# usb_shield.net
KiCad netlist of a schematic drawn in EAGLE
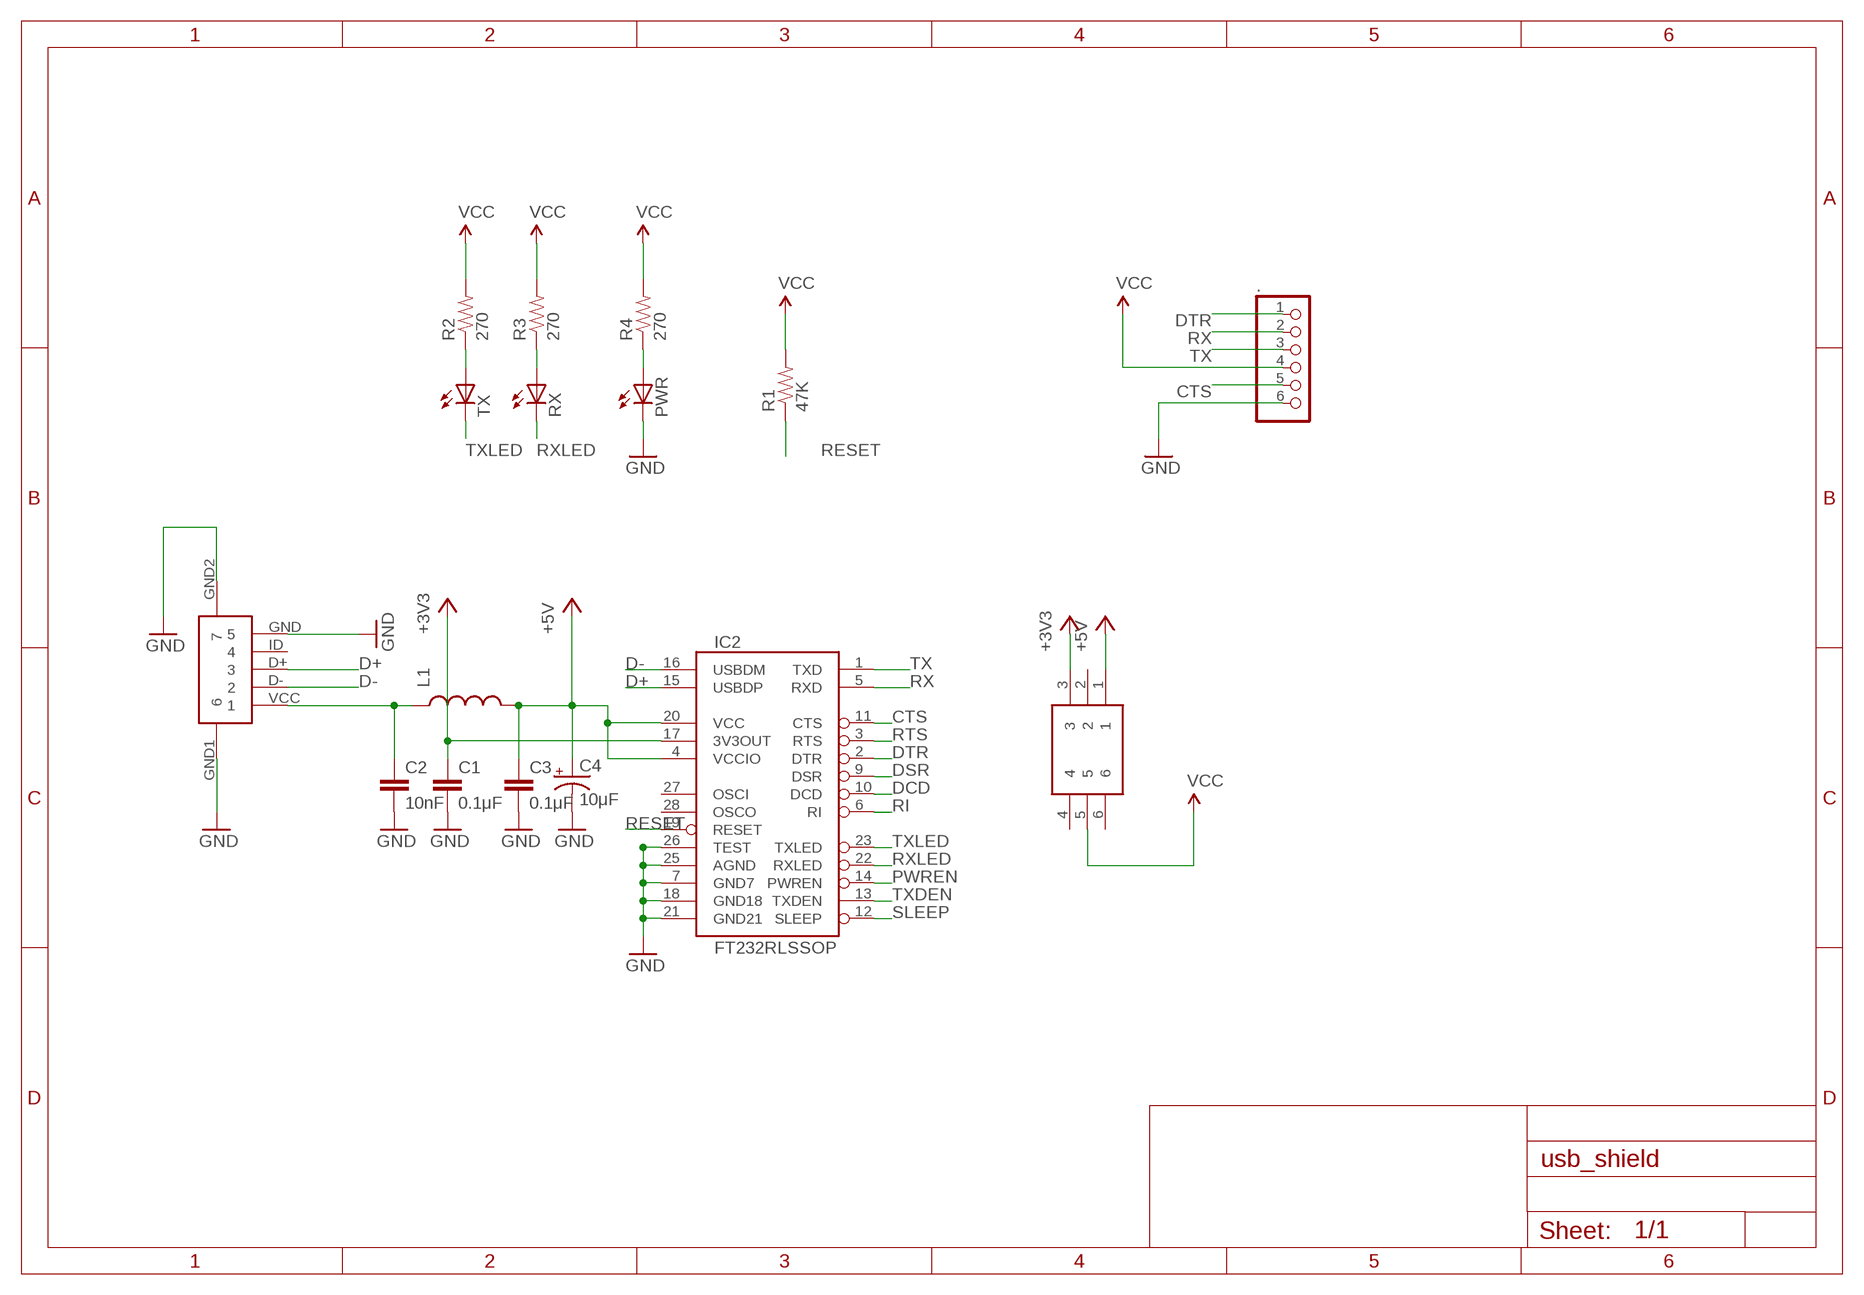
[diagram p0: schematic, sheet 1]

(export (version "E")
  (design (tool "Eeschema 10.0.6"))
  (components
    (comp (ref ".")
      (value "PINHD-1X6")
      (footprint "eagle-import:1X06")
      (libsource (lib "eagle-import") (part "PINHD-1X6"))
    )
    (comp (ref "C1")
      (value "0.1μF")
      (footprint "eagle-import:0603-CAP")
      (libsource (lib "eagle-import") (part "CAP0603-CAP"))
    )
    (comp (ref "C2")
      (value "10nF")
      (footprint "eagle-import:0603-CAP")
      (libsource (lib "eagle-import") (part "CAP0603-CAP"))
    )
    (comp (ref "C3")
      (value "0.1μF")
      (footprint "eagle-import:0603-CAP")
      (libsource (lib "eagle-import") (part "CAP0603-CAP"))
    )
    (comp (ref "C4")
      (value "10μF")
      (footprint "eagle-import:EIA3216")
      (libsource (lib "eagle-import") (part "CAP_POL1206"))
    )
    (comp (ref "IC2")
      (value "FT232RLSSOP")
      (footprint "eagle-import:SSOP28DB")
      (libsource (lib "eagle-import") (part "FT232RLSSOP"))
    )
    (comp (ref "L1")
      (value "INDUCTOR0603")
      (footprint "eagle-import:0603")
      (libsource (lib "eagle-import") (part "INDUCTOR0603"))
    )
    (comp (ref "PWR")
      (value "LEDCHIP-LED0805")
      (footprint "eagle-import:CHIP-LED0805")
      (libsource (lib "eagle-import") (part "LEDCHIP-LED0805"))
    )
    (comp (ref "R1")
      (value "47K")
      (footprint "eagle-import:0603-RES")
      (libsource (lib "eagle-import") (part "RESISTOR0603-RES"))
    )
    (comp (ref "R2")
      (value "270")
      (footprint "eagle-import:0603-RES")
      (libsource (lib "eagle-import") (part "RESISTOR0603-RES"))
    )
    (comp (ref "R3")
      (value "270")
      (footprint "eagle-import:0603-RES")
      (libsource (lib "eagle-import") (part "RESISTOR0603-RES"))
    )
    (comp (ref "R4")
      (value "270")
      (footprint "eagle-import:0603-RES")
      (libsource (lib "eagle-import") (part "RESISTOR0603-RES"))
    )
    (comp (ref "RX")
      (value "LEDCHIP-LED0805")
      (footprint "eagle-import:CHIP-LED0805")
      (libsource (lib "eagle-import") (part "LEDCHIP-LED0805"))
    )
    (comp (ref "TX")
      (value "LEDCHIP-LED0805")
      (footprint "eagle-import:CHIP-LED0805")
      (libsource (lib "eagle-import") (part "LEDCHIP-LED0805"))
    )
    (comp (ref "U$1")
      (value "USB-MICRO-B-FEMALE")
      (footprint "eagle-import:USB-MICRO-B-FEMALE")
      (libsource (lib "eagle-import") (part "USB-MICRO-B-FEMALE"))
    )
    (comp (ref "U$2")
      (value "C&K_JS202011SCQN")
      (footprint "eagle-import:C&K_JS202011SCQN")
      (libsource (lib "eagle-import") (part "C&K_JS202011SCQN"))
    )
  )
  (nets
    (net (code "1") (name "+3V3") (class "Default")
      (node (ref "C1") (pin "1") (pinfunction "1_1") (pintype "passive"))
      (node (ref "IC2") (pin "17") (pinfunction "3V3OUT_17") (pintype "output"))
      (node (ref "U$2") (pin "3") (pinfunction "3_3") (pintype "bidirectional"))
    )
    (net (code "2") (name "+5V") (class "Default")
      (node (ref "C3") (pin "1") (pinfunction "1_1") (pintype "passive"))
      (node (ref "C4") (pin "A") (pinfunction "+_A") (pintype "passive"))
      (node (ref "IC2") (pin "20") (pinfunction "VCC_20") (pintype "power_in"))
      (node (ref "IC2") (pin "4") (pinfunction "VCCIO_4") (pintype "power_in"))
      (node (ref "L1") (pin "2") (pinfunction "2_2") (pintype "passive"))
      (node (ref "U$2") (pin "1") (pinfunction "1_1") (pintype "bidirectional"))
    )
    (net (code "3") (name "/CTS") (class "Default")
      (node (ref ".") (pin "5") (pinfunction "5_5") (pintype "passive"))
      (node (ref "IC2") (pin "11") (pinfunction "CTS_11") (pintype "input"))
    )
    (net (code "4") (name "/D+") (class "Default")
      (node (ref "IC2") (pin "15") (pinfunction "USBDP_15") (pintype "bidirectional"))
      (node (ref "U$1") (pin "D+") (pinfunction "3_D+") (pintype "bidirectional"))
    )
    (net (code "5") (name "/D-") (class "Default")
      (node (ref "IC2") (pin "16") (pinfunction "USBDM_16") (pintype "bidirectional"))
      (node (ref "U$1") (pin "D-") (pinfunction "2_D-") (pintype "bidirectional"))
    )
    (net (code "6") (name "/DCD") (class "Default")
      (node (ref "IC2") (pin "10") (pinfunction "DCD_10") (pintype "input"))
    )
    (net (code "7") (name "/DSR") (class "Default")
      (node (ref "IC2") (pin "9") (pinfunction "DSR_9") (pintype "input"))
    )
    (net (code "8") (name "/DTR") (class "Default")
      (node (ref ".") (pin "1") (pinfunction "1_1") (pintype "passive"))
      (node (ref "IC2") (pin "2") (pinfunction "DTR_2") (pintype "output"))
    )
    (net (code "9") (name "/PWREN") (class "Default")
      (node (ref "IC2") (pin "14") (pinfunction "PWREN_14") (pintype "input"))
    )
    (net (code "10") (name "/RESET") (class "Default")
      (node (ref "IC2") (pin "19") (pinfunction "RESET_19") (pintype "input"))
      (node (ref "R1") (pin "1") (pinfunction "1_1") (pintype "passive"))
    )
    (net (code "11") (name "/RI") (class "Default")
      (node (ref "IC2") (pin "6") (pinfunction "RI_6") (pintype "input"))
    )
    (net (code "12") (name "/RTS") (class "Default")
      (node (ref "IC2") (pin "3") (pinfunction "RTS_3") (pintype "output"))
    )
    (net (code "13") (name "/RX") (class "Default")
      (node (ref ".") (pin "2") (pinfunction "2_2") (pintype "passive"))
      (node (ref "IC2") (pin "5") (pinfunction "RXD_5") (pintype "input"))
    )
    (net (code "14") (name "/RXLED") (class "Default")
      (node (ref "IC2") (pin "22") (pinfunction "RXLED_22") (pintype "input"))
      (node (ref "RX") (pin "C") (pinfunction "C_C") (pintype "passive"))
    )
    (net (code "15") (name "/SLEEP") (class "Default")
      (node (ref "IC2") (pin "12") (pinfunction "SLEEP_12") (pintype "input"))
    )
    (net (code "16") (name "/TX") (class "Default")
      (node (ref ".") (pin "3") (pinfunction "3_3") (pintype "passive"))
      (node (ref "IC2") (pin "1") (pinfunction "TXD_1") (pintype "output"))
    )
    (net (code "17") (name "/TXDEN") (class "Default")
      (node (ref "IC2") (pin "13") (pinfunction "TXDEN_13") (pintype "input"))
    )
    (net (code "18") (name "/TXLED") (class "Default")
      (node (ref "IC2") (pin "23") (pinfunction "TXLED_23") (pintype "input"))
      (node (ref "TX") (pin "C") (pinfunction "C_C") (pintype "passive"))
    )
    (net (code "19") (name "GND") (class "Default")
      (node (ref ".") (pin "6") (pinfunction "6_6") (pintype "passive"))
      (node (ref "C1") (pin "2") (pinfunction "2_2") (pintype "passive"))
      (node (ref "C2") (pin "2") (pinfunction "2_2") (pintype "passive"))
      (node (ref "C3") (pin "2") (pinfunction "2_2") (pintype "passive"))
      (node (ref "C4") (pin "C") (pinfunction "-_C") (pintype "passive"))
      (node (ref "IC2") (pin "18") (pinfunction "GND18_18") (pintype "power_in"))
      (node (ref "IC2") (pin "21") (pinfunction "GND21_21") (pintype "power_in"))
      (node (ref "IC2") (pin "25") (pinfunction "AGND_25") (pintype "power_in"))
      (node (ref "IC2") (pin "26") (pinfunction "TEST_26") (pintype "input"))
      (node (ref "IC2") (pin "7") (pinfunction "GND7_7") (pintype "power_in"))
      (node (ref "PWR") (pin "C") (pinfunction "C_C") (pintype "passive"))
      (node (ref "U$1") (pin "GND") (pinfunction "5_GND") (pintype "bidirectional"))
      (node (ref "U$1") (pin "GND1") (pinfunction "6_GND1") (pintype "bidirectional"))
      (node (ref "U$1") (pin "GND2") (pinfunction "7_GND2") (pintype "bidirectional"))
    )
    (net (code "20") (name "Net-(PWR-PadA)") (class "Default")
      (node (ref "PWR") (pin "A") (pinfunction "A_A") (pintype "passive"))
      (node (ref "R4") (pin "1") (pinfunction "1_1") (pintype "passive"))
    )
    (net (code "21") (name "Net-(R2-Pad1)") (class "Default")
      (node (ref "R2") (pin "1") (pinfunction "1_1") (pintype "passive"))
      (node (ref "TX") (pin "A") (pinfunction "A_A") (pintype "passive"))
    )
    (net (code "22") (name "Net-(R3-Pad1)") (class "Default")
      (node (ref "R3") (pin "1") (pinfunction "1_1") (pintype "passive"))
      (node (ref "RX") (pin "A") (pinfunction "A_A") (pintype "passive"))
    )
    (net (code "23") (name "Net-(U$1-1)") (class "Default")
      (node (ref "C2") (pin "1") (pinfunction "1_1") (pintype "passive"))
      (node (ref "L1") (pin "1") (pinfunction "1_1") (pintype "passive"))
      (node (ref "U$1") (pin "VCC") (pinfunction "1_VCC") (pintype "bidirectional"))
    )
    (net (code "24") (name "VCC") (class "Default")
      (node (ref ".") (pin "4") (pinfunction "4_4") (pintype "passive"))
      (node (ref "R1") (pin "2") (pinfunction "2_2") (pintype "passive"))
      (node (ref "R2") (pin "2") (pinfunction "2_2") (pintype "passive"))
      (node (ref "R3") (pin "2") (pinfunction "2_2") (pintype "passive"))
      (node (ref "R4") (pin "2") (pinfunction "2_2") (pintype "passive"))
      (node (ref "U$2") (pin "5") (pinfunction "5_5") (pintype "bidirectional"))
    )
    (net (code "25") (name "unconnected-(IC2-OSCI-Pad27)") (class "Default")
      (node (ref "IC2") (pin "27") (pinfunction "OSCI_27") (pintype "input"))
    )
    (net (code "26") (name "unconnected-(IC2-OSCO-Pad28)") (class "Default")
      (node (ref "IC2") (pin "28") (pinfunction "OSCO_28") (pintype "output"))
    )
    (net (code "27") (name "unconnected-(U$1-4-PadID)") (class "Default")
      (node (ref "U$1") (pin "ID") (pinfunction "4_ID") (pintype "bidirectional"))
    )
    (net (code "28") (name "unconnected-(U$2-Pad2)") (class "Default")
      (node (ref "U$2") (pin "2") (pinfunction "2_2") (pintype "bidirectional"))
    )
    (net (code "29") (name "unconnected-(U$2-Pad4)") (class "Default")
      (node (ref "U$2") (pin "4") (pinfunction "4_4") (pintype "bidirectional"))
    )
    (net (code "30") (name "unconnected-(U$2-Pad6)") (class "Default")
      (node (ref "U$2") (pin "6") (pinfunction "6_6") (pintype "bidirectional"))
    )
  )
)
